# MB1297_MCU2.net
KiCad netlist of a schematic drawn in Altium Designer
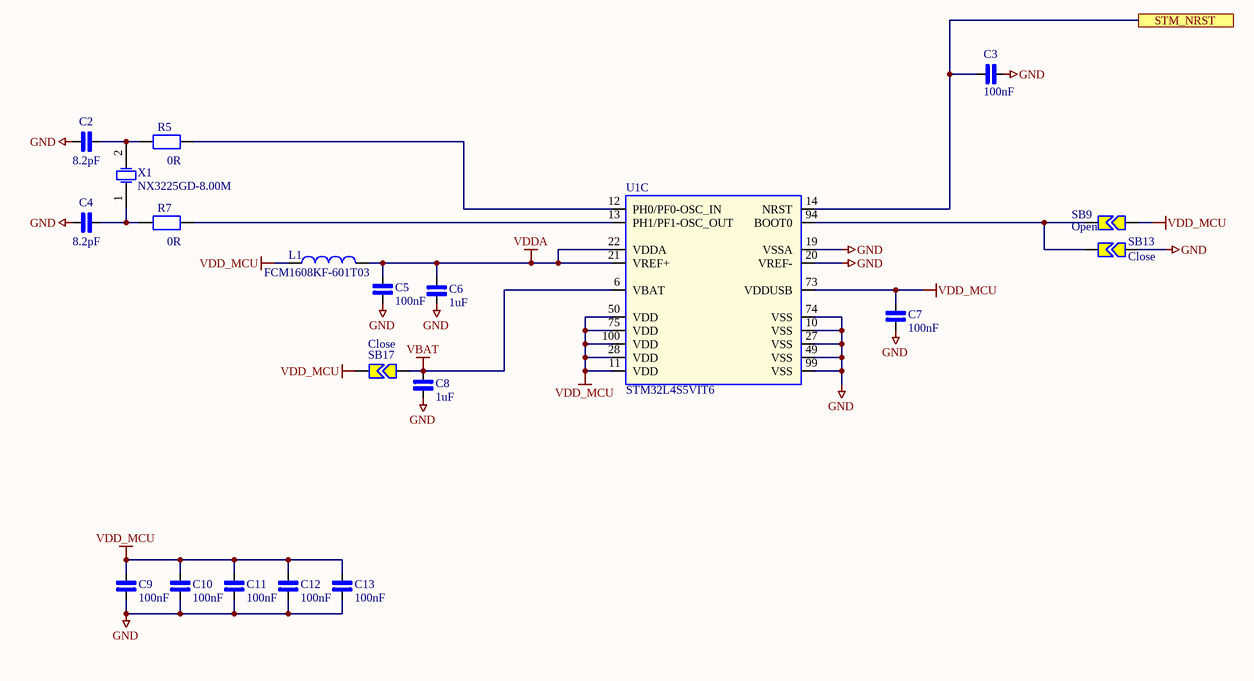
[diagram p0: MB1297_MCU2.SchDoc]

(export (version "E")
  (design (tool "Eeschema 10.0.6"))
  (components
    (comp (ref "C2")
      (value "8.2pF")
      (footprint "0402")
      (description "Capacitor_not polarized")
      (libsource (lib "ST_Lib3D") (part "CAP_NPOL"))
    )
    (comp (ref "C3")
      (value "100nF")
      (footprint "0402")
      (description "Capacitor_not polarized")
      (libsource (lib "ST_Lib3D") (part "CAP_NPOL"))
    )
    (comp (ref "C4")
      (value "8.2pF")
      (footprint "0402")
      (description "Capacitor_not polarized")
      (libsource (lib "ST_Lib3D") (part "CAP_NPOL"))
    )
    (comp (ref "C5")
      (value "100nF")
      (footprint "0402")
      (description "Capacitor_not polarized")
      (libsource (lib "ST_Lib3D") (part "CAP_NPOL"))
    )
    (comp (ref "C6")
      (value "1uF")
      (footprint "0402")
      (description "Capacitor_not polarized")
      (libsource (lib "ST_Lib3D") (part "CAP_NPOL"))
    )
    (comp (ref "C7")
      (value "100nF")
      (footprint "0402")
      (description "Capacitor_not polarized")
      (libsource (lib "ST_Lib3D") (part "CAP_NPOL"))
    )
    (comp (ref "C8")
      (value "1uF")
      (footprint "0402")
      (description "Capacitor_not polarized")
      (libsource (lib "ST_Lib3D") (part "CAP_NPOL"))
    )
    (comp (ref "C9")
      (value "100nF")
      (footprint "0402")
      (description "Capacitor_not polarized")
      (libsource (lib "MB1297") (part "CAP_NPOL"))
    )
    (comp (ref "C10")
      (value "100nF")
      (footprint "0402")
      (description "Capacitor_not polarized")
      (libsource (lib "MB1297") (part "CAP_NPOL"))
    )
    (comp (ref "C11")
      (value "100nF")
      (footprint "0402")
      (description "Capacitor_not polarized")
      (libsource (lib "MB1297") (part "CAP_NPOL"))
    )
    (comp (ref "C12")
      (value "100nF")
      (footprint "0402")
      (description "Capacitor_not polarized")
      (libsource (lib "MB1297") (part "CAP_NPOL"))
    )
    (comp (ref "C13")
      (value "100nF")
      (footprint "0402")
      (description "Capacitor_not polarized")
      (libsource (lib "MB1297") (part "CAP_NPOL"))
    )
    (comp (ref "L1")
      (value "FCM1608KF-601T03")
      (footprint "0603L")
      (description "Inductor")
      (fields (field (name "PUBLISHER") "Altium Limited"))
      (libsource (lib "Miscellaneous Devices") (part "Inductor"))
    )
    (comp (ref "R5")
      (value "0R")
      (footprint "0402")
      (description "Resistor")
      (libsource (lib "Lib3D_Altium10_Schlib") (part "RES"))
    )
    (comp (ref "R7")
      (value "0R")
      (footprint "0402")
      (description "Resistor")
      (libsource (lib "Lib3D_Altium10_Schlib") (part "RES"))
    )
    (comp (ref "SB9")
      (value "Open")
      (footprint "SB")
      (description "Solder Jumper")
      (fields (field (name "PUBLISHER") "Altium Limited"))
      (libsource (lib "ST_Lib3D") (part "Strap2"))
    )
    (comp (ref "SB13")
      (value "Close")
      (footprint "SB")
      (description "Solder Jumper")
      (fields (field (name "PUBLISHER") "Altium Limited"))
      (libsource (lib "ST_Lib3D") (part "Strap2"))
    )
    (comp (ref "SB17")
      (value "Close")
      (footprint "SB")
      (description "Solder Jumper")
      (fields (field (name "PUBLISHER") "Altium Limited"))
      (libsource (lib "Lib3D_Altium10_Schlib") (part "Strap2"))
    )
    (comp (ref "U1")
      (value "STM32L4S5VIT6")
      (footprint "LQFP100 14x14x1.6")
      (description "STM32L475VGTx")
      (libsource (lib "ST_Lib3D") (part "STM32L475VGTx"))
    )
    (comp (ref "X1")
      (value "NX3225GD-8.00M")
      (footprint "CRY_NX3225GD_2P")
      (description "Crystal 8Mhz, 8pF, -+50PPM, SMD")
      (libsource (lib "MCD_TEMP_PCH") (part "XTAL_8M_NX3225GD"))
    )
  )
  (nets
    (net (code "1") (name "/STM_NRST") (class "Default")
      (node (ref "C3") (pin "2") (pinfunction "2_2") (pintype "passive"))
      (node (ref "U1") (pin "14") (pinfunction "NRST_14") (pintype "passive"))
    )
    (net (code "2") (name "GND") (class "Default")
      (node (ref "C10") (pin "2") (pinfunction "2_2") (pintype "passive"))
      (node (ref "C11") (pin "2") (pinfunction "2_2") (pintype "passive"))
      (node (ref "C12") (pin "2") (pinfunction "2_2") (pintype "passive"))
      (node (ref "C13") (pin "2") (pinfunction "2_2") (pintype "passive"))
      (node (ref "C2") (pin "2") (pinfunction "2_2") (pintype "passive"))
      (node (ref "C3") (pin "1") (pinfunction "1_1") (pintype "passive"))
      (node (ref "C4") (pin "2") (pinfunction "2_2") (pintype "passive"))
      (node (ref "C5") (pin "2") (pinfunction "2_2") (pintype "passive"))
      (node (ref "C6") (pin "1") (pinfunction "1_1") (pintype "passive"))
      (node (ref "C7") (pin "2") (pinfunction "2_2") (pintype "passive"))
      (node (ref "C8") (pin "1") (pinfunction "1_1") (pintype "passive"))
      (node (ref "C9") (pin "2") (pinfunction "2_2") (pintype "passive"))
      (node (ref "SB13") (pin "1") (pinfunction "1_1") (pintype "passive"))
      (node (ref "U1") (pin "10") (pinfunction "VSS_10") (pintype "passive"))
      (node (ref "U1") (pin "19") (pinfunction "VSSA_19") (pintype "passive"))
      (node (ref "U1") (pin "20") (pinfunction "VREF-_20") (pintype "passive"))
      (node (ref "U1") (pin "27") (pinfunction "VSS_27") (pintype "passive"))
      (node (ref "U1") (pin "49") (pinfunction "VSS_49") (pintype "passive"))
      (node (ref "U1") (pin "74") (pinfunction "VSS_74") (pintype "passive"))
      (node (ref "U1") (pin "99") (pinfunction "VSS_99") (pintype "passive"))
    )
    (net (code "3") (name "Net-(U1C-BOOT0)") (class "Default")
      (node (ref "SB13") (pin "2") (pinfunction "2_2") (pintype "passive"))
      (node (ref "SB9") (pin "2") (pinfunction "2_2") (pintype "passive"))
      (node (ref "U1") (pin "94") (pinfunction "BOOT0_94") (pintype "passive"))
    )
    (net (code "4") (name "Net-(U1C-PH0{slash}PF0-OSC_IN)") (class "Default")
      (node (ref "R5") (pin "1") (pinfunction "1_1") (pintype "passive"))
      (node (ref "U1") (pin "12") (pinfunction "PH0/PF0-OSC_IN_12") (pintype "passive"))
    )
    (net (code "5") (name "Net-(U1C-PH1{slash}PF1-OSC_OUT)") (class "Default")
      (node (ref "R7") (pin "1") (pinfunction "1_1") (pintype "passive"))
      (node (ref "U1") (pin "13") (pinfunction "PH1/PF1-OSC_OUT_13") (pintype "passive"))
    )
    (net (code "6") (name "Net-(X1-OSC1)") (class "Default")
      (node (ref "C4") (pin "1") (pinfunction "1_1") (pintype "passive"))
      (node (ref "R7") (pin "2") (pinfunction "2_2") (pintype "passive"))
      (node (ref "X1") (pin "1") (pinfunction "OSC1_1") (pintype "passive"))
    )
    (net (code "7") (name "Net-(X1-OSC2)") (class "Default")
      (node (ref "C2") (pin "1") (pinfunction "1_1") (pintype "passive"))
      (node (ref "R5") (pin "2") (pinfunction "2_2") (pintype "passive"))
      (node (ref "X1") (pin "2") (pinfunction "OSC2_2") (pintype "passive"))
    )
    (net (code "8") (name "VBAT") (class "Default")
      (node (ref "C8") (pin "2") (pinfunction "2_2") (pintype "passive"))
      (node (ref "SB17") (pin "2") (pinfunction "2_2") (pintype "passive"))
      (node (ref "U1") (pin "6") (pinfunction "VBAT_6") (pintype "passive"))
    )
    (net (code "9") (name "VDDA") (class "Default")
      (node (ref "C5") (pin "1") (pinfunction "1_1") (pintype "passive"))
      (node (ref "C6") (pin "2") (pinfunction "2_2") (pintype "passive"))
      (node (ref "L1") (pin "2") (pinfunction "2_2") (pintype "passive"))
      (node (ref "U1") (pin "21") (pinfunction "VREF+_21") (pintype "passive"))
      (node (ref "U1") (pin "22") (pinfunction "VDDA_22") (pintype "passive"))
    )
    (net (code "10") (name "VDD_MCU") (class "Default")
      (node (ref "C10") (pin "1") (pinfunction "1_1") (pintype "passive"))
      (node (ref "C11") (pin "1") (pinfunction "1_1") (pintype "passive"))
      (node (ref "C12") (pin "1") (pinfunction "1_1") (pintype "passive"))
      (node (ref "C13") (pin "1") (pinfunction "1_1") (pintype "passive"))
      (node (ref "C7") (pin "1") (pinfunction "1_1") (pintype "passive"))
      (node (ref "C9") (pin "1") (pinfunction "1_1") (pintype "passive"))
      (node (ref "L1") (pin "1") (pinfunction "1_1") (pintype "passive"))
      (node (ref "SB17") (pin "1") (pinfunction "1_1") (pintype "passive"))
      (node (ref "SB9") (pin "1") (pinfunction "1_1") (pintype "passive"))
      (node (ref "U1") (pin "100") (pinfunction "VDD_100") (pintype "passive"))
      (node (ref "U1") (pin "11") (pinfunction "VDD_11") (pintype "passive"))
      (node (ref "U1") (pin "28") (pinfunction "VDD_28") (pintype "passive"))
      (node (ref "U1") (pin "50") (pinfunction "VDD_50") (pintype "passive"))
      (node (ref "U1") (pin "73") (pinfunction "VDDUSB_73") (pintype "passive"))
      (node (ref "U1") (pin "75") (pinfunction "VDD_75") (pintype "passive"))
    )
  )
)
